# mcu2.net
KiCad netlist of a schematic drawn in Altium Designer
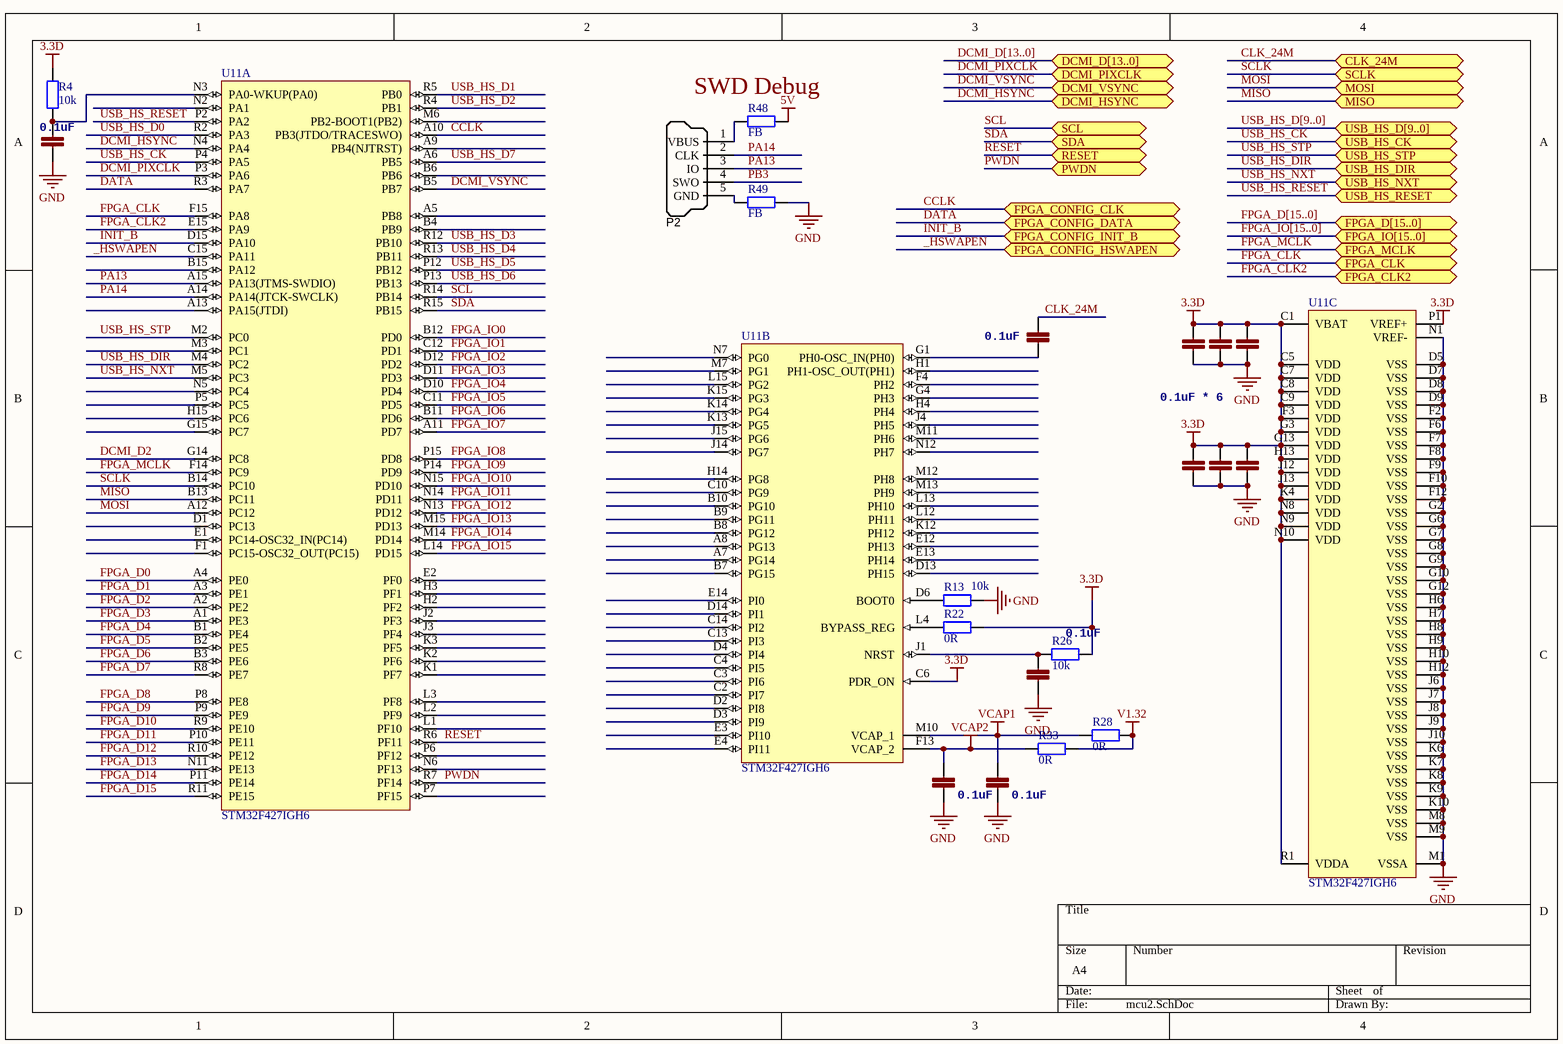
[diagram p0: mcu2.SchDoc]

(export (version "E")
  (design (tool "Eeschema 10.0.6"))
  (components
    (comp (ref "C4")
      (value "0.1uF * 6")
      (footprint "0402")
      (description "<b>Capacitor</b>\nStandard 0603 ceramic capacitor, and 0.1\" leaded capacitor.")
      (fields (field (name "PARTNO") "CC0402ZRY5V7BB104"))
      (libsource (lib "*") (part "CAP0402-CAP"))
    )
    (comp (ref "C5")
      (value "0.1uF")
      (footprint "0402")
      (description "<b>Capacitor</b>\nStandard 0603 ceramic capacitor, and 0.1\" leaded capacitor.")
      (fields (field (name "PARTNO") "CC0402ZRY5V7BB104"))
      (libsource (lib "pixhawk2") (part "CAP0402-CAP"))
    )
    (comp (ref "C6")
      (value "0.1uF")
      (footprint "0402")
      (description "<b>Capacitor</b>\nStandard 0603 ceramic capacitor, and 0.1\" leaded capacitor.")
      (fields (field (name "PARTNO") "CC0402ZRY5V7BB104"))
      (libsource (lib "pixhawk2") (part "CAP0402-CAP"))
    )
    (comp (ref "C12")
      (value "0.1uF")
      (footprint "0402")
      (description "<b>Capacitor</b>\nStandard 0603 ceramic capacitor, and 0.1\" leaded capacitor.")
      (fields (field (name "PARTNO") "CC0402ZRY5V7BB104"))
      (libsource (lib "*") (part "CAP0402-CAP"))
    )
    (comp (ref "C13")
      (value "0.1uF")
      (footprint "0402")
      (description "<b>Capacitor</b>\nStandard 0603 ceramic capacitor, and 0.1\" leaded capacitor.")
      (fields (field (name "PARTNO") "CC0402ZRY5V7BB104"))
      (libsource (lib "pixhawk2") (part "CAP0402-CAP"))
    )
    (comp (ref "C14")
      (value "0.1uF")
      (footprint "0402")
      (description "<b>Capacitor</b>\nStandard 0603 ceramic capacitor, and 0.1\" leaded capacitor.")
      (fields (field (name "PARTNO") "CC0402ZRY5V7BB104"))
      (libsource (lib "pixhawk2") (part "CAP0402-CAP"))
    )
    (comp (ref "C15")
      (value "0.1uF")
      (footprint "0402")
      (description "<b>Capacitor</b>\nStandard 0603 ceramic capacitor, and 0.1\" leaded capacitor.")
      (fields (field (name "PARTNO") "CC0402ZRY5V7BB104"))
      (libsource (lib "*") (part "CAP0402-CAP"))
    )
    (comp (ref "C35")
      (value "0.1uF * 6")
      (footprint "0402")
      (description "<b>Capacitor</b>\nStandard 0603 ceramic capacitor, and 0.1\" leaded capacitor.")
      (fields (field (name "PARTNO") "CC0402ZRY5V7BB104"))
      (libsource (lib "*") (part "CAP0402-CAP"))
    )
    (comp (ref "C36")
      (value "0.1uF")
      (footprint "0402")
      (description "<b>Capacitor</b>\nStandard 0603 ceramic capacitor, and 0.1\" leaded capacitor.")
      (fields (field (name "PARTNO") "CC0402ZRY5V7BB104"))
      (libsource (lib "*") (part "CAP0402-CAP"))
    )
    (comp (ref "C37")
      (value "0.1uF")
      (footprint "0402")
      (description "<b>Capacitor</b>\nStandard 0603 ceramic capacitor, and 0.1\" leaded capacitor.")
      (fields (field (name "PARTNO") "CC0402ZRY5V7BB104"))
      (libsource (lib "*") (part "CAP0402-CAP"))
    )
    (comp (ref "C38")
      (value "0.1uF")
      (footprint "0402")
      (description "<b>Capacitor</b>\nStandard 0603 ceramic capacitor, and 0.1\" leaded capacitor.")
      (fields (field (name "PARTNO") "CC0402ZRY5V7BB104"))
      (libsource (lib "*") (part "CAP0402-CAP"))
    )
    (comp (ref "P2")
      (value "SWD_MicroUSB")
      (footprint "MICRO-YZX")
      (description "Connector SMD USB Micro Type B middle mount")
      (libsource (lib "sch") (part "SWD_MicroUSB"))
    )
    (comp (ref "R4")
      (value "10k")
      (footprint "0402")
      (description "Resistor")
      (fields (field (name "PUBLISHER") "Altium Limited"))
      (libsource (lib "Miscellaneous Devices") (part "Res2"))
    )
    (comp (ref "R13")
      (value "10k")
      (footprint "0402")
      (description "Resistor")
      (fields (field (name "PUBLISHER") "Altium Limited"))
      (libsource (lib "") (part "Res2_1"))
    )
    (comp (ref "R22")
      (value "0R")
      (footprint "0402")
      (description "Resistor")
      (fields (field (name "PUBLISHER") "Altium Limited"))
      (libsource (lib "") (part "Res2_1"))
    )
    (comp (ref "R26")
      (value "10k")
      (footprint "0402")
      (description "Resistor")
      (fields (field (name "PUBLISHER") "Altium Limited"))
      (libsource (lib "") (part "Res2_2"))
    )
    (comp (ref "R28")
      (value "0R")
      (footprint "0402")
      (description "Resistor")
      (fields (field (name "PUBLISHER") "Altium Limited"))
      (libsource (lib "") (part "Res2_2"))
    )
    (comp (ref "R33")
      (value "0R")
      (footprint "0402")
      (description "Resistor")
      (fields (field (name "PUBLISHER") "Altium Limited"))
      (libsource (lib "") (part "Res2_2"))
    )
    (comp (ref "R48")
      (value "FB")
      (footprint "0603")
      (description "Resistor")
      (fields (field (name "PUBLISHER") "Altium Limited"))
      (libsource (lib "") (part "Res2_1"))
    )
    (comp (ref "R49")
      (value "FB")
      (footprint "0603")
      (description "Resistor")
      (fields (field (name "PUBLISHER") "Altium Limited"))
      (libsource (lib "") (part "Res2_1"))
    )
    (comp (ref "U11")
      (value "STM32F427IGH6")
      (footprint "STM-UFBGA176+25_M")
      (fields (field (name "MANUFACTURER") "STMicroelectronics"))
      (libsource (lib "STMicroelectronics STM32 F4") (part "STM32F427IGH6"))
    )
  )
  (nets
    (net (code "16") (name "/CCLK") (class "Default")
      (node (ref "U11") (pin "A10") (pinfunction "PB3(JTDO/TRACESWO)_A10") (pintype "bidirectional"))
    )
    (net (code "17") (name "/CLK_24M") (class "Default")
      (node (ref "C15") (pin "2") (pinfunction "2_2") (pintype "passive"))
    )
    (net (code "18") (name "/DATA") (class "Default")
      (node (ref "U11") (pin "R3") (pinfunction "PA7_R3") (pintype "bidirectional"))
    )
    (net (code "19") (name "/DCMI_D2") (class "Default")
      (node (ref "U11") (pin "G14") (pinfunction "PC8_G14") (pintype "bidirectional"))
    )
    (net (code "21") (name "/DCMI_HSYNC") (class "Default")
      (node (ref "U11") (pin "N4") (pinfunction "PA4_N4") (pintype "bidirectional"))
    )
    (net (code "22") (name "/DCMI_PIXCLK") (class "Default")
      (node (ref "U11") (pin "P3") (pinfunction "PA6_P3") (pintype "bidirectional"))
    )
    (net (code "23") (name "/DCMI_VSYNC") (class "Default")
      (node (ref "U11") (pin "B5") (pinfunction "PB7_B5") (pintype "bidirectional"))
    )
    (net (code "24") (name "/FPGA_CLK") (class "Default")
      (node (ref "U11") (pin "F15") (pinfunction "PA8_F15") (pintype "bidirectional"))
    )
    (net (code "25") (name "/FPGA_CLK2") (class "Default")
      (node (ref "U11") (pin "E15") (pinfunction "PA9_E15") (pintype "bidirectional"))
    )
    (net (code "26") (name "/FPGA_D0") (class "Default")
      (node (ref "U11") (pin "A4") (pinfunction "PE0_A4") (pintype "bidirectional"))
    )
    (net (code "27") (name "/FPGA_D1") (class "Default")
      (node (ref "U11") (pin "A3") (pinfunction "PE1_A3") (pintype "bidirectional"))
    )
    (net (code "28") (name "/FPGA_D2") (class "Default")
      (node (ref "U11") (pin "A2") (pinfunction "PE2_A2") (pintype "bidirectional"))
    )
    (net (code "29") (name "/FPGA_D3") (class "Default")
      (node (ref "U11") (pin "A1") (pinfunction "PE3_A1") (pintype "bidirectional"))
    )
    (net (code "30") (name "/FPGA_D4") (class "Default")
      (node (ref "U11") (pin "B1") (pinfunction "PE4_B1") (pintype "bidirectional"))
    )
    (net (code "31") (name "/FPGA_D5") (class "Default")
      (node (ref "U11") (pin "B2") (pinfunction "PE5_B2") (pintype "bidirectional"))
    )
    (net (code "32") (name "/FPGA_D6") (class "Default")
      (node (ref "U11") (pin "B3") (pinfunction "PE6_B3") (pintype "bidirectional"))
    )
    (net (code "33") (name "/FPGA_D7") (class "Default")
      (node (ref "U11") (pin "R8") (pinfunction "PE7_R8") (pintype "bidirectional"))
    )
    (net (code "34") (name "/FPGA_D8") (class "Default")
      (node (ref "U11") (pin "P8") (pinfunction "PE8_P8") (pintype "bidirectional"))
    )
    (net (code "35") (name "/FPGA_D9") (class "Default")
      (node (ref "U11") (pin "P9") (pinfunction "PE9_P9") (pintype "bidirectional"))
    )
    (net (code "36") (name "/FPGA_D10") (class "Default")
      (node (ref "U11") (pin "R9") (pinfunction "PE10_R9") (pintype "bidirectional"))
    )
    (net (code "37") (name "/FPGA_D11") (class "Default")
      (node (ref "U11") (pin "P10") (pinfunction "PE11_P10") (pintype "bidirectional"))
    )
    (net (code "38") (name "/FPGA_D12") (class "Default")
      (node (ref "U11") (pin "R10") (pinfunction "PE12_R10") (pintype "bidirectional"))
    )
    (net (code "39") (name "/FPGA_D13") (class "Default")
      (node (ref "U11") (pin "N11") (pinfunction "PE13_N11") (pintype "bidirectional"))
    )
    (net (code "40") (name "/FPGA_D14") (class "Default")
      (node (ref "U11") (pin "P11") (pinfunction "PE14_P11") (pintype "bidirectional"))
    )
    (net (code "41") (name "/FPGA_D15") (class "Default")
      (node (ref "U11") (pin "R11") (pinfunction "PE15_R11") (pintype "bidirectional"))
    )
    (net (code "43") (name "/FPGA_IO0") (class "Default")
      (node (ref "U11") (pin "B12") (pinfunction "PD0_B12") (pintype "bidirectional"))
    )
    (net (code "44") (name "/FPGA_IO1") (class "Default")
      (node (ref "U11") (pin "C12") (pinfunction "PD1_C12") (pintype "bidirectional"))
    )
    (net (code "45") (name "/FPGA_IO2") (class "Default")
      (node (ref "U11") (pin "D12") (pinfunction "PD2_D12") (pintype "bidirectional"))
    )
    (net (code "46") (name "/FPGA_IO3") (class "Default")
      (node (ref "U11") (pin "D11") (pinfunction "PD3_D11") (pintype "bidirectional"))
    )
    (net (code "47") (name "/FPGA_IO4") (class "Default")
      (node (ref "U11") (pin "D10") (pinfunction "PD4_D10") (pintype "bidirectional"))
    )
    (net (code "48") (name "/FPGA_IO5") (class "Default")
      (node (ref "U11") (pin "C11") (pinfunction "PD5_C11") (pintype "bidirectional"))
    )
    (net (code "49") (name "/FPGA_IO6") (class "Default")
      (node (ref "U11") (pin "B11") (pinfunction "PD6_B11") (pintype "bidirectional"))
    )
    (net (code "50") (name "/FPGA_IO7") (class "Default")
      (node (ref "U11") (pin "A11") (pinfunction "PD7_A11") (pintype "bidirectional"))
    )
    (net (code "51") (name "/FPGA_IO8") (class "Default")
      (node (ref "U11") (pin "P15") (pinfunction "PD8_P15") (pintype "bidirectional"))
    )
    (net (code "52") (name "/FPGA_IO9") (class "Default")
      (node (ref "U11") (pin "P14") (pinfunction "PD9_P14") (pintype "bidirectional"))
    )
    (net (code "53") (name "/FPGA_IO10") (class "Default")
      (node (ref "U11") (pin "N15") (pinfunction "PD10_N15") (pintype "bidirectional"))
    )
    (net (code "54") (name "/FPGA_IO11") (class "Default")
      (node (ref "U11") (pin "N14") (pinfunction "PD11_N14") (pintype "bidirectional"))
    )
    (net (code "55") (name "/FPGA_IO12") (class "Default")
      (node (ref "U11") (pin "N13") (pinfunction "PD12_N13") (pintype "bidirectional"))
    )
    (net (code "56") (name "/FPGA_IO13") (class "Default")
      (node (ref "U11") (pin "M15") (pinfunction "PD13_M15") (pintype "bidirectional"))
    )
    (net (code "57") (name "/FPGA_IO14") (class "Default")
      (node (ref "U11") (pin "M14") (pinfunction "PD14_M14") (pintype "bidirectional"))
    )
    (net (code "58") (name "/FPGA_IO15") (class "Default")
      (node (ref "U11") (pin "L14") (pinfunction "PD15_L14") (pintype "bidirectional"))
    )
    (net (code "60") (name "/FPGA_MCLK") (class "Default")
      (node (ref "U11") (pin "F14") (pinfunction "PC9_F14") (pintype "bidirectional"))
    )
    (net (code "61") (name "/INIT_B") (class "Default")
      (node (ref "U11") (pin "D15") (pinfunction "PA10_D15") (pintype "bidirectional"))
    )
    (net (code "62") (name "/MISO") (class "Default")
      (node (ref "U11") (pin "B13") (pinfunction "PC11_B13") (pintype "bidirectional"))
    )
    (net (code "63") (name "/MOSI") (class "Default")
      (node (ref "U11") (pin "A12") (pinfunction "PC12_A12") (pintype "bidirectional"))
    )
    (net (code "64") (name "/PA13") (class "Default")
      (node (ref "P2") (pin "3") (pinfunction "IO_3") (pintype "passive"))
      (node (ref "U11") (pin "A15") (pinfunction "PA13(JTMS-SWDIO)_A15") (pintype "bidirectional"))
    )
    (net (code "65") (name "/PA14") (class "Default")
      (node (ref "P2") (pin "2") (pinfunction "CLK_2") (pintype "passive"))
      (node (ref "U11") (pin "A14") (pinfunction "PA14(JTCK-SWCLK)_A14") (pintype "bidirectional"))
    )
    (net (code "66") (name "/PB3") (class "Default")
      (node (ref "P2") (pin "4") (pinfunction "SWO_4") (pintype "passive"))
    )
    (net (code "67") (name "/PWDN") (class "Default")
      (node (ref "U11") (pin "R7") (pinfunction "PF14_R7") (pintype "bidirectional"))
    )
    (net (code "68") (name "/RESET") (class "Default")
      (node (ref "U11") (pin "R6") (pinfunction "PF11_R6") (pintype "bidirectional"))
    )
    (net (code "69") (name "/SCL") (class "Default")
      (node (ref "U11") (pin "R14") (pinfunction "PB14_R14") (pintype "bidirectional"))
    )
    (net (code "70") (name "/SCLK") (class "Default")
      (node (ref "U11") (pin "B14") (pinfunction "PC10_B14") (pintype "bidirectional"))
    )
    (net (code "71") (name "/SDA") (class "Default")
      (node (ref "U11") (pin "R15") (pinfunction "PB15_R15") (pintype "bidirectional"))
    )
    (net (code "72") (name "/USB_HS_CK") (class "Default")
      (node (ref "U11") (pin "P4") (pinfunction "PA5_P4") (pintype "bidirectional"))
    )
    (net (code "73") (name "/USB_HS_D0") (class "Default")
      (node (ref "U11") (pin "R2") (pinfunction "PA3_R2") (pintype "bidirectional"))
    )
    (net (code "74") (name "/USB_HS_D1") (class "Default")
      (node (ref "U11") (pin "R5") (pinfunction "PB0_R5") (pintype "bidirectional"))
    )
    (net (code "75") (name "/USB_HS_D2") (class "Default")
      (node (ref "U11") (pin "R4") (pinfunction "PB1_R4") (pintype "bidirectional"))
    )
    (net (code "76") (name "/USB_HS_D3") (class "Default")
      (node (ref "U11") (pin "R12") (pinfunction "PB10_R12") (pintype "bidirectional"))
    )
    (net (code "77") (name "/USB_HS_D4") (class "Default")
      (node (ref "U11") (pin "R13") (pinfunction "PB11_R13") (pintype "bidirectional"))
    )
    (net (code "78") (name "/USB_HS_D5") (class "Default")
      (node (ref "U11") (pin "P12") (pinfunction "PB12_P12") (pintype "bidirectional"))
    )
    (net (code "79") (name "/USB_HS_D6") (class "Default")
      (node (ref "U11") (pin "P13") (pinfunction "PB13_P13") (pintype "bidirectional"))
    )
    (net (code "80") (name "/USB_HS_D7") (class "Default")
      (node (ref "U11") (pin "A6") (pinfunction "PB5_A6") (pintype "bidirectional"))
    )
    (net (code "81") (name "/USB_HS_DIR") (class "Default")
      (node (ref "U11") (pin "M4") (pinfunction "PC2_M4") (pintype "bidirectional"))
    )
    (net (code "83") (name "/USB_HS_NXT") (class "Default")
      (node (ref "U11") (pin "M5") (pinfunction "PC3_M5") (pintype "bidirectional"))
    )
    (net (code "84") (name "/USB_HS_RESET") (class "Default")
      (node (ref "U11") (pin "P2") (pinfunction "PA2_P2") (pintype "bidirectional"))
    )
    (net (code "85") (name "/USB_HS_STP") (class "Default")
      (node (ref "U11") (pin "M2") (pinfunction "PC0_M2") (pintype "bidirectional"))
    )
    (net (code "86") (name "/_HSWAPEN") (class "Default")
      (node (ref "U11") (pin "C15") (pinfunction "PA11_C15") (pintype "bidirectional"))
    )
    (net (code "87") (name "3.3D") (class "Default")
      (node (ref "C13") (pin "2") (pinfunction "2_2") (pintype "passive"))
      (node (ref "C14") (pin "2") (pinfunction "2_2") (pintype "passive"))
      (node (ref "C35") (pin "2") (pinfunction "2_2") (pintype "passive"))
      (node (ref "C4") (pin "2") (pinfunction "2_2") (pintype "passive"))
      (node (ref "C5") (pin "2") (pinfunction "2_2") (pintype "passive"))
      (node (ref "C6") (pin "2") (pinfunction "2_2") (pintype "passive"))
      (node (ref "R22") (pin "1") (pinfunction "1_1") (pintype "passive"))
      (node (ref "R26") (pin "2") (pinfunction "2_2") (pintype "passive"))
      (node (ref "R4") (pin "1") (pinfunction "1_1") (pintype "passive"))
      (node (ref "U11") (pin "C1") (pinfunction "VBAT_C1") (pintype "power_in"))
      (node (ref "U11") (pin "C5") (pinfunction "VDD_C5") (pintype "power_in"))
      (node (ref "U11") (pin "C6") (pinfunction "PDR_ON_C6") (pintype "input"))
      (node (ref "U11") (pin "C7") (pinfunction "VDD_C7") (pintype "power_in"))
      (node (ref "U11") (pin "C8") (pinfunction "VDD_C8") (pintype "power_in"))
      (node (ref "U11") (pin "C9") (pinfunction "VDD_C9") (pintype "power_in"))
      (node (ref "U11") (pin "F3") (pinfunction "VDD_F3") (pintype "power_in"))
      (node (ref "U11") (pin "G13") (pinfunction "VDD_G13") (pintype "power_in"))
      (node (ref "U11") (pin "G3") (pinfunction "VDD_G3") (pintype "power_in"))
      (node (ref "U11") (pin "H13") (pinfunction "VDD_H13") (pintype "power_in"))
      (node (ref "U11") (pin "J12") (pinfunction "VDD_J12") (pintype "power_in"))
      (node (ref "U11") (pin "J13") (pinfunction "VDD_J13") (pintype "power_in"))
      (node (ref "U11") (pin "K4") (pinfunction "VDD_K4") (pintype "power_in"))
      (node (ref "U11") (pin "N10") (pinfunction "VDD_N10") (pintype "power_in"))
      (node (ref "U11") (pin "N8") (pinfunction "VDD_N8") (pintype "power_in"))
      (node (ref "U11") (pin "N9") (pinfunction "VDD_N9") (pintype "power_in"))
      (node (ref "U11") (pin "P1") (pinfunction "VREF+_P1") (pintype "power_in"))
      (node (ref "U11") (pin "R1") (pinfunction "VDDA_R1") (pintype "power_in"))
    )
    (net (code "88") (name "5V") (class "Default")
      (node (ref "R48") (pin "1") (pinfunction "1_1") (pintype "passive"))
    )
    (net (code "89") (name "GND") (class "Default")
      (node (ref "C12") (pin "1") (pinfunction "1_1") (pintype "passive"))
      (node (ref "C13") (pin "1") (pinfunction "1_1") (pintype "passive"))
      (node (ref "C14") (pin "1") (pinfunction "1_1") (pintype "passive"))
      (node (ref "C35") (pin "1") (pinfunction "1_1") (pintype "passive"))
      (node (ref "C36") (pin "1") (pinfunction "1_1") (pintype "passive"))
      (node (ref "C37") (pin "1") (pinfunction "1_1") (pintype "passive"))
      (node (ref "C38") (pin "1") (pinfunction "1_1") (pintype "passive"))
      (node (ref "C4") (pin "1") (pinfunction "1_1") (pintype "passive"))
      (node (ref "C5") (pin "1") (pinfunction "1_1") (pintype "passive"))
      (node (ref "C6") (pin "1") (pinfunction "1_1") (pintype "passive"))
      (node (ref "R13") (pin "1") (pinfunction "1_1") (pintype "passive"))
      (node (ref "R49") (pin "1") (pinfunction "1_1") (pintype "passive"))
      (node (ref "U11") (pin "D5") (pinfunction "VSS_D5") (pintype "power_in"))
      (node (ref "U11") (pin "D7") (pinfunction "VSS_D7") (pintype "power_in"))
      (node (ref "U11") (pin "D8") (pinfunction "VSS_D8") (pintype "power_in"))
      (node (ref "U11") (pin "D9") (pinfunction "VSS_D9") (pintype "power_in"))
      (node (ref "U11") (pin "F10") (pinfunction "VSS_F10") (pintype "power_in"))
      (node (ref "U11") (pin "F12") (pinfunction "VSS_F12") (pintype "power_in"))
      (node (ref "U11") (pin "F2") (pinfunction "VSS_F2") (pintype "power_in"))
      (node (ref "U11") (pin "F6") (pinfunction "VSS_F6") (pintype "power_in"))
      (node (ref "U11") (pin "F7") (pinfunction "VSS_F7") (pintype "power_in"))
      (node (ref "U11") (pin "F8") (pinfunction "VSS_F8") (pintype "power_in"))
      (node (ref "U11") (pin "F9") (pinfunction "VSS_F9") (pintype "power_in"))
      (node (ref "U11") (pin "G10") (pinfunction "VSS_G10") (pintype "power_in"))
      (node (ref "U11") (pin "G12") (pinfunction "VSS_G12") (pintype "power_in"))
      (node (ref "U11") (pin "G2") (pinfunction "VSS_G2") (pintype "power_in"))
      (node (ref "U11") (pin "G6") (pinfunction "VSS_G6") (pintype "power_in"))
      (node (ref "U11") (pin "G7") (pinfunction "VSS_G7") (pintype "power_in"))
      (node (ref "U11") (pin "G8") (pinfunction "VSS_G8") (pintype "power_in"))
      (node (ref "U11") (pin "G9") (pinfunction "VSS_G9") (pintype "power_in"))
      (node (ref "U11") (pin "H10") (pinfunction "VSS_H10") (pintype "power_in"))
      (node (ref "U11") (pin "H12") (pinfunction "VSS_H12") (pintype "power_in"))
      (node (ref "U11") (pin "H6") (pinfunction "VSS_H6") (pintype "power_in"))
      (node (ref "U11") (pin "H7") (pinfunction "VSS_H7") (pintype "power_in"))
      (node (ref "U11") (pin "H8") (pinfunction "VSS_H8") (pintype "power_in"))
      (node (ref "U11") (pin "H9") (pinfunction "VSS_H9") (pintype "power_in"))
      (node (ref "U11") (pin "J10") (pinfunction "VSS_J10") (pintype "power_in"))
      (node (ref "U11") (pin "J6") (pinfunction "VSS_J6") (pintype "power_in"))
      (node (ref "U11") (pin "J7") (pinfunction "VSS_J7") (pintype "power_in"))
      (node (ref "U11") (pin "J8") (pinfunction "VSS_J8") (pintype "power_in"))
      (node (ref "U11") (pin "J9") (pinfunction "VSS_J9") (pintype "power_in"))
      (node (ref "U11") (pin "K10") (pinfunction "VSS_K10") (pintype "power_in"))
      (node (ref "U11") (pin "K6") (pinfunction "VSS_K6") (pintype "power_in"))
      (node (ref "U11") (pin "K7") (pinfunction "VSS_K7") (pintype "power_in"))
      (node (ref "U11") (pin "K8") (pinfunction "VSS_K8") (pintype "power_in"))
      (node (ref "U11") (pin "K9") (pinfunction "VSS_K9") (pintype "power_in"))
      (node (ref "U11") (pin "M1") (pinfunction "VSSA_M1") (pintype "power_in"))
      (node (ref "U11") (pin "M8") (pinfunction "VSS_M8") (pintype "power_in"))
      (node (ref "U11") (pin "M9") (pinfunction "VSS_M9") (pintype "power_in"))
      (node (ref "U11") (pin "N1") (pinfunction "VREF-_N1") (pintype "power_in"))
    )
    (net (code "90") (name "Net-(P2-GND)") (class "Default")
      (node (ref "P2") (pin "5") (pinfunction "GND_5") (pintype "passive"))
      (node (ref "R49") (pin "2") (pinfunction "2_2") (pintype "passive"))
    )
    (net (code "91") (name "Net-(P2-VBUS)") (class "Default")
      (node (ref "P2") (pin "1") (pinfunction "VBUS_1") (pintype "passive"))
      (node (ref "R48") (pin "2") (pinfunction "2_2") (pintype "passive"))
    )
    (net (code "92") (name "Net-(U11A-PA0-WKUP(PA0))") (class "Default")
      (node (ref "C12") (pin "2") (pinfunction "2_2") (pintype "passive"))
      (node (ref "R4") (pin "2") (pinfunction "2_2") (pintype "passive"))
      (node (ref "U11") (pin "N3") (pinfunction "PA0-WKUP(PA0)_N3") (pintype "bidirectional"))
    )
    (net (code "93") (name "Net-(U11B-BOOT0)") (class "Default")
      (node (ref "R13") (pin "2") (pinfunction "2_2") (pintype "passive"))
      (node (ref "U11") (pin "D6") (pinfunction "BOOT0_D6") (pintype "input"))
    )
    (net (code "94") (name "Net-(U11B-BYPASS_REG)") (class "Default")
      (node (ref "R22") (pin "2") (pinfunction "2_2") (pintype "passive"))
      (node (ref "U11") (pin "L4") (pinfunction "BYPASS_REG_L4") (pintype "input"))
    )
    (net (code "95") (name "Net-(U11B-NRST)") (class "Default")
      (node (ref "C36") (pin "2") (pinfunction "2_2") (pintype "passive"))
      (node (ref "R26") (pin "1") (pinfunction "1_1") (pintype "passive"))
      (node (ref "U11") (pin "J1") (pinfunction "NRST_J1") (pintype "bidirectional"))
    )
    (net (code "96") (name "Net-(U11B-PH0-OSC_IN(PH0))") (class "Default")
      (node (ref "C15") (pin "1") (pinfunction "1_1") (pintype "passive"))
      (node (ref "U11") (pin "G1") (pinfunction "PH0-OSC_IN(PH0)_G1") (pintype "bidirectional"))
    )
    (net (code "97") (name "V1.32") (class "Default")
      (node (ref "R28") (pin "2") (pinfunction "2_2") (pintype "passive"))
      (node (ref "R33") (pin "2") (pinfunction "2_2") (pintype "passive"))
    )
    (net (code "98") (name "VCAP1") (class "Default")
      (node (ref "C38") (pin "2") (pinfunction "2_2") (pintype "passive"))
      (node (ref "R28") (pin "1") (pinfunction "1_1") (pintype "passive"))
      (node (ref "U11") (pin "M10") (pinfunction "VCAP_1_M10") (pintype "power_in"))
    )
    (net (code "99") (name "VCAP2") (class "Default")
      (node (ref "C37") (pin "2") (pinfunction "2_2") (pintype "passive"))
      (node (ref "R33") (pin "1") (pinfunction "1_1") (pintype "passive"))
      (node (ref "U11") (pin "F13") (pinfunction "VCAP_2_F13") (pintype "power_in"))
    )
    (net (code "100") (name "unconnected-(U11A-PA1-PadN2)") (class "Default")
      (node (ref "U11") (pin "N2") (pinfunction "PA1_N2") (pintype "bidirectional"))
    )
    (net (code "101") (name "unconnected-(U11A-PA12-PadB15)") (class "Default")
      (node (ref "U11") (pin "B15") (pinfunction "PA12_B15") (pintype "bidirectional"))
    )
    (net (code "102") (name "unconnected-(U11A-PA15(JTDI)-PadA13)") (class "Default")
      (node (ref "U11") (pin "A13") (pinfunction "PA15(JTDI)_A13") (pintype "bidirectional"))
    )
    (net (code "103") (name "unconnected-(U11A-PB2-BOOT1(PB2)-PadM6)") (class "Default")
      (node (ref "U11") (pin "M6") (pinfunction "PB2-BOOT1(PB2)_M6") (pintype "bidirectional"))
    )
    (net (code "104") (name "unconnected-(U11A-PB4(NJTRST)-PadA9)") (class "Default")
      (node (ref "U11") (pin "A9") (pinfunction "PB4(NJTRST)_A9") (pintype "bidirectional"))
    )
    (net (code "105") (name "unconnected-(U11A-PB6-PadB6)") (class "Default")
      (node (ref "U11") (pin "B6") (pinfunction "PB6_B6") (pintype "bidirectional"))
    )
    (net (code "106") (name "unconnected-(U11A-PB8-PadA5)") (class "Default")
      (node (ref "U11") (pin "A5") (pinfunction "PB8_A5") (pintype "bidirectional"))
    )
    (net (code "107") (name "unconnected-(U11A-PB9-PadB4)") (class "Default")
      (node (ref "U11") (pin "B4") (pinfunction "PB9_B4") (pintype "bidirectional"))
    )
    (net (code "108") (name "unconnected-(U11A-PC1-PadM3)") (class "Default")
      (node (ref "U11") (pin "M3") (pinfunction "PC1_M3") (pintype "bidirectional"))
    )
    (net (code "109") (name "unconnected-(U11A-PC4-PadN5)") (class "Default")
      (node (ref "U11") (pin "N5") (pinfunction "PC4_N5") (pintype "bidirectional"))
    )
    (net (code "110") (name "unconnected-(U11A-PC5-PadP5)") (class "Default")
      (node (ref "U11") (pin "P5") (pinfunction "PC5_P5") (pintype "bidirectional"))
    )
    (net (code "111") (name "unconnected-(U11A-PC6-PadH15)") (class "Default")
      (node (ref "U11") (pin "H15") (pinfunction "PC6_H15") (pintype "bidirectional"))
    )
    (net (code "112") (name "unconnected-(U11A-PC7-PadG15)") (class "Default")
      (node (ref "U11") (pin "G15") (pinfunction "PC7_G15") (pintype "bidirectional"))
    )
    (net (code "113") (name "unconnected-(U11A-PC13-PadD1)") (class "Default")
      (node (ref "U11") (pin "D1") (pinfunction "PC13_D1") (pintype "bidirectional"))
    )
    (net (code "114") (name "unconnected-(U11A-PC14-OSC32_IN(PC14)-PadE1)") (class "Default")
      (node (ref "U11") (pin "E1") (pinfunction "PC14-OSC32_IN(PC14)_E1") (pintype "bidirectional"))
    )
    (net (code "115") (name "unconnected-(U11A-PC15-OSC32_OUT(PC15)-PadF1)") (class "Default")
      (node (ref "U11") (pin "F1") (pinfunction "PC15-OSC32_OUT(PC15)_F1") (pintype "bidirectional"))
    )
    (net (code "116") (name "unconnected-(U11A-PF0-PadE2)") (class "Default")
      (node (ref "U11") (pin "E2") (pinfunction "PF0_E2") (pintype "bidirectional"))
    )
    (net (code "117") (name "unconnected-(U11A-PF1-PadH3)") (class "Default")
      (node (ref "U11") (pin "H3") (pinfunction "PF1_H3") (pintype "bidirectional"))
    )
    (net (code "118") (name "unconnected-(U11A-PF2-PadH2)") (class "Default")
      (node (ref "U11") (pin "H2") (pinfunction "PF2_H2") (pintype "bidirectional"))
    )
    (net (code "119") (name "unconnected-(U11A-PF3-PadJ2)") (class "Default")
      (node (ref "U11") (pin "J2") (pinfunction "PF3_J2") (pintype "bidirectional"))
    )
    (net (code "120") (name "unconnected-(U11A-PF4-PadJ3)") (class "Default")
      (node (ref "U11") (pin "J3") (pinfunction "PF4_J3") (pintype "bidirectional"))
    )
    (net (code "121") (name "unconnected-(U11A-PF5-PadK3)") (class "Default")
      (node (ref "U11") (pin "K3") (pinfunction "PF5_K3") (pintype "bidirectional"))
    )
    (net (code "122") (name "unconnected-(U11A-PF6-PadK2)") (class "Default")
      (node (ref "U11") (pin "K2") (pinfunction "PF6_K2") (pintype "bidirectional"))
    )
    (net (code "123") (name "unconnected-(U11A-PF7-PadK1)") (class "Default")
      (node (ref "U11") (pin "K1") (pinfunction "PF7_K1") (pintype "bidirectional"))
    )
    (net (code "124") (name "unconnected-(U11A-PF8-PadL3)") (class "Default")
      (node (ref "U11") (pin "L3") (pinfunction "PF8_L3") (pintype "bidirectional"))
    )
    (net (code "125") (name "unconnected-(U11A-PF9-PadL2)") (class "Default")
      (node (ref "U11") (pin "L2") (pinfunction "PF9_L2") (pintype "bidirectional"))
    )
    (net (code "126") (name "unconnected-(U11A-PF10-PadL1)") (class "Default")
      (node (ref "U11") (pin "L1") (pinfunction "PF10_L1") (pintype "bidirectional"))
    )
    (net (code "127") (name "unconnected-(U11A-PF12-PadP6)") (class "Default")
      (node (ref "U11") (pin "P6") (pinfunction "PF12_P6") (pintype "bidirectional"))
    )
    (net (code "128") (name "unconnected-(U11A-PF13-PadN6)") (class "Default")
      (node (ref "U11") (pin "N6") (pinfunction "PF13_N6") (pintype "bidirectional"))
    )
    (net (code "129") (name "unconnected-(U11A-PF15-PadP7)") (class "Default")
      (node (ref "U11") (pin "P7") (pinfunction "PF15_P7") (pintype "bidirectional"))
    )
    (net (code "130") (name "unconnected-(U11B-PG0-PadN7)") (class "Default")
      (node (ref "U11") (pin "N7") (pinfunction "PG0_N7") (pintype "bidirectional"))
    )
    (net (code "131") (name "unconnected-(U11B-PG1-PadM7)") (class "Default")
      (node (ref "U11") (pin "M7") (pinfunction "PG1_M7") (pintype "bidirectional"))
    )
    (net (code "132") (name "unconnected-(U11B-PG2-PadL15)") (class "Default")
      (node (ref "U11") (pin "L15") (pinfunction "PG2_L15") (pintype "bidirectional"))
    )
    (net (code "133") (name "unconnected-(U11B-PG3-PadK15)") (class "Default")
      (node (ref "U11") (pin "K15") (pinfunction "PG3_K15") (pintype "bidirectional"))
    )
    (net (code "134") (name "unconnected-(U11B-PG4-PadK14)") (class "Default")
      (node (ref "U11") (pin "K14") (pinfunction "PG4_K14") (pintype "bidirectional"))
    )
    (net (code "135") (name "unconnected-(U11B-PG5-PadK13)") (class "Default")
      (node (ref "U11") (pin "K13") (pinfunction "PG5_K13") (pintype "bidirectional"))
    )
    (net (code "136") (name "unconnected-(U11B-PG6-PadJ15)") (class "Default")
      (node (ref "U11") (pin "J15") (pinfunction "PG6_J15") (pintype "bidirectional"))
    )
    (net (code "137") (name "unconnected-(U11B-PG7-PadJ14)") (class "Default")
      (node (ref "U11") (pin "J14") (pinfunction "PG7_J14") (pintype "bidirectional"))
    )
    (net (code "138") (name "unconnected-(U11B-PG8-PadH14)") (class "Default")
      (node (ref "U11") (pin "H14") (pinfunction "PG8_H14") (pintype "bidirectional"))
    )
    (net (code "139") (name "unconnected-(U11B-PG9-PadC10)") (class "Default")
      (node (ref "U11") (pin "C10") (pinfunction "PG9_C10") (pintype "bidirectional"))
    )
    (net (code "140") (name "unconnected-(U11B-PG10-PadB10)") (class "Default")
      (node (ref "U11") (pin "B10") (pinfunction "PG10_B10") (pintype "bidirectional"))
    )
    (net (code "141") (name "unconnected-(U11B-PG11-PadB9)") (class "Default")
      (node (ref "U11") (pin "B9") (pinfunction "PG11_B9") (pintype "bidirectional"))
    )
    (net (code "142") (name "unconnected-(U11B-PG12-PadB8)") (class "Default")
      (node (ref "U11") (pin "B8") (pinfunction "PG12_B8") (pintype "bidirectional"))
    )
    (net (code "143") (name "unconnected-(U11B-PG13-PadA8)") (class "Default")
      (node (ref "U11") (pin "A8") (pinfunction "PG13_A8") (pintype "bidirectional"))
    )
    (net (code "144") (name "unconnected-(U11B-PG14-PadA7)") (class "Default")
      (node (ref "U11") (pin "A7") (pinfunction "PG14_A7") (pintype "bidirectional"))
    )
    (net (code "145") (name "unconnected-(U11B-PG15-PadB7)") (class "Default")
      (node (ref "U11") (pin "B7") (pinfunction "PG15_B7") (pintype "bidirectional"))
    )
    (net (code "146") (name "unconnected-(U11B-PH1-OSC_OUT(PH1)-PadH1)") (class "Default")
      (node (ref "U11") (pin "H1") (pinfunction "PH1-OSC_OUT(PH1)_H1") (pintype "bidirectional"))
    )
    (net (code "147") (name "unconnected-(U11B-PH2-PadF4)") (class "Default")
      (node (ref "U11") (pin "F4") (pinfunction "PH2_F4") (pintype "bidirectional"))
    )
    (net (code "148") (name "unconnected-(U11B-PH3-PadG4)") (class "Default")
      (node (ref "U11") (pin "G4") (pinfunction "PH3_G4") (pintype "bidirectional"))
    )
    (net (code "149") (name "unconnected-(U11B-PH4-PadH4)") (class "Default")
      (node (ref "U11") (pin "H4") (pinfunction "PH4_H4") (pintype "bidirectional"))
    )
    (net (code "150") (name "unconnected-(U11B-PH5-PadJ4)") (class "Default")
      (node (ref "U11") (pin "J4") (pinfunction "PH5_J4") (pintype "bidirectional"))
    )
    (net (code "151") (name "unconnected-(U11B-PH6-PadM11)") (class "Default")
      (node (ref "U11") (pin "M11") (pinfunction "PH6_M11") (pintype "bidirectional"))
    )
    (net (code "152") (name "unconnected-(U11B-PH7-PadN12)") (class "Default")
      (node (ref "U11") (pin "N12") (pinfunction "PH7_N12") (pintype "bidirectional"))
    )
    (net (code "153") (name "unconnected-(U11B-PH8-PadM12)") (class "Default")
      (node (ref "U11") (pin "M12") (pinfunction "PH8_M12") (pintype "bidirectional"))
    )
    (net (code "154") (name "unconnected-(U11B-PH9-PadM13)") (class "Default")
      (node (ref "U11") (pin "M13") (pinfunction "PH9_M13") (pintype "bidirectional"))
    )
    (net (code "155") (name "unconnected-(U11B-PH10-PadL13)") (class "Default")
      (node (ref "U11") (pin "L13") (pinfunction "PH10_L13") (pintype "bidirectional"))
    )
    (net (code "156") (name "unconnected-(U11B-PH11-PadL12)") (class "Default")
      (node (ref "U11") (pin "L12") (pinfunction "PH11_L12") (pintype "bidirectional"))
    )
    (net (code "157") (name "unconnected-(U11B-PH12-PadK12)") (class "Default")
      (node (ref "U11") (pin "K12") (pinfunction "PH12_K12") (pintype "bidirectional"))
    )
    (net (code "158") (name "unconnected-(U11B-PH13-PadE12)") (class "Default")
      (node (ref "U11") (pin "E12") (pinfunction "PH13_E12") (pintype "bidirectional"))
    )
    (net (code "159") (name "unconnected-(U11B-PH14-PadE13)") (class "Default")
      (node (ref "U11") (pin "E13") (pinfunction "PH14_E13") (pintype "bidirectional"))
    )
    (net (code "160") (name "unconnected-(U11B-PH15-PadD13)") (class "Default")
      (node (ref "U11") (pin "D13") (pinfunction "PH15_D13") (pintype "bidirectional"))
    )
    (net (code "161") (name "unconnected-(U11B-PI0-PadE14)") (class "Default")
      (node (ref "U11") (pin "E14") (pinfunction "PI0_E14") (pintype "bidirectional"))
    )
    (net (code "162") (name "unconnected-(U11B-PI1-PadD14)") (class "Default")
      (node (ref "U11") (pin "D14") (pinfunction "PI1_D14") (pintype "bidirectional"))
    )
    (net (code "163") (name "unconnected-(U11B-PI2-PadC14)") (class "Default")
      (node (ref "U11") (pin "C14") (pinfunction "PI2_C14") (pintype "bidirectional"))
    )
    (net (code "164") (name "unconnected-(U11B-PI3-PadC13)") (class "Default")
      (node (ref "U11") (pin "C13") (pinfunction "PI3_C13") (pintype "bidirectional"))
    )
    (net (code "165") (name "unconnected-(U11B-PI4-PadD4)") (class "Default")
      (node (ref "U11") (pin "D4") (pinfunction "PI4_D4") (pintype "bidirectional"))
    )
    (net (code "166") (name "unconnected-(U11B-PI5-PadC4)") (class "Default")
      (node (ref "U11") (pin "C4") (pinfunction "PI5_C4") (pintype "bidirectional"))
    )
    (net (code "167") (name "unconnected-(U11B-PI6-PadC3)") (class "Default")
      (node (ref "U11") (pin "C3") (pinfunction "PI6_C3") (pintype "bidirectional"))
    )
    (net (code "168") (name "unconnected-(U11B-PI7-PadC2)") (class "Default")
      (node (ref "U11") (pin "C2") (pinfunction "PI7_C2") (pintype "bidirectional"))
    )
    (net (code "169") (name "unconnected-(U11B-PI8-PadD2)") (class "Default")
      (node (ref "U11") (pin "D2") (pinfunction "PI8_D2") (pintype "bidirectional"))
    )
    (net (code "170") (name "unconnected-(U11B-PI9-PadD3)") (class "Default")
      (node (ref "U11") (pin "D3") (pinfunction "PI9_D3") (pintype "bidirectional"))
    )
    (net (code "171") (name "unconnected-(U11B-PI10-PadE3)") (class "Default")
      (node (ref "U11") (pin "E3") (pinfunction "PI10_E3") (pintype "bidirectional"))
    )
    (net (code "172") (name "unconnected-(U11B-PI11-PadE4)") (class "Default")
      (node (ref "U11") (pin "E4") (pinfunction "PI11_E4") (pintype "bidirectional"))
    )
  )
)
